# 05_SERVO_FAN.net
KiCad netlist of a schematic drawn in Altium Designer
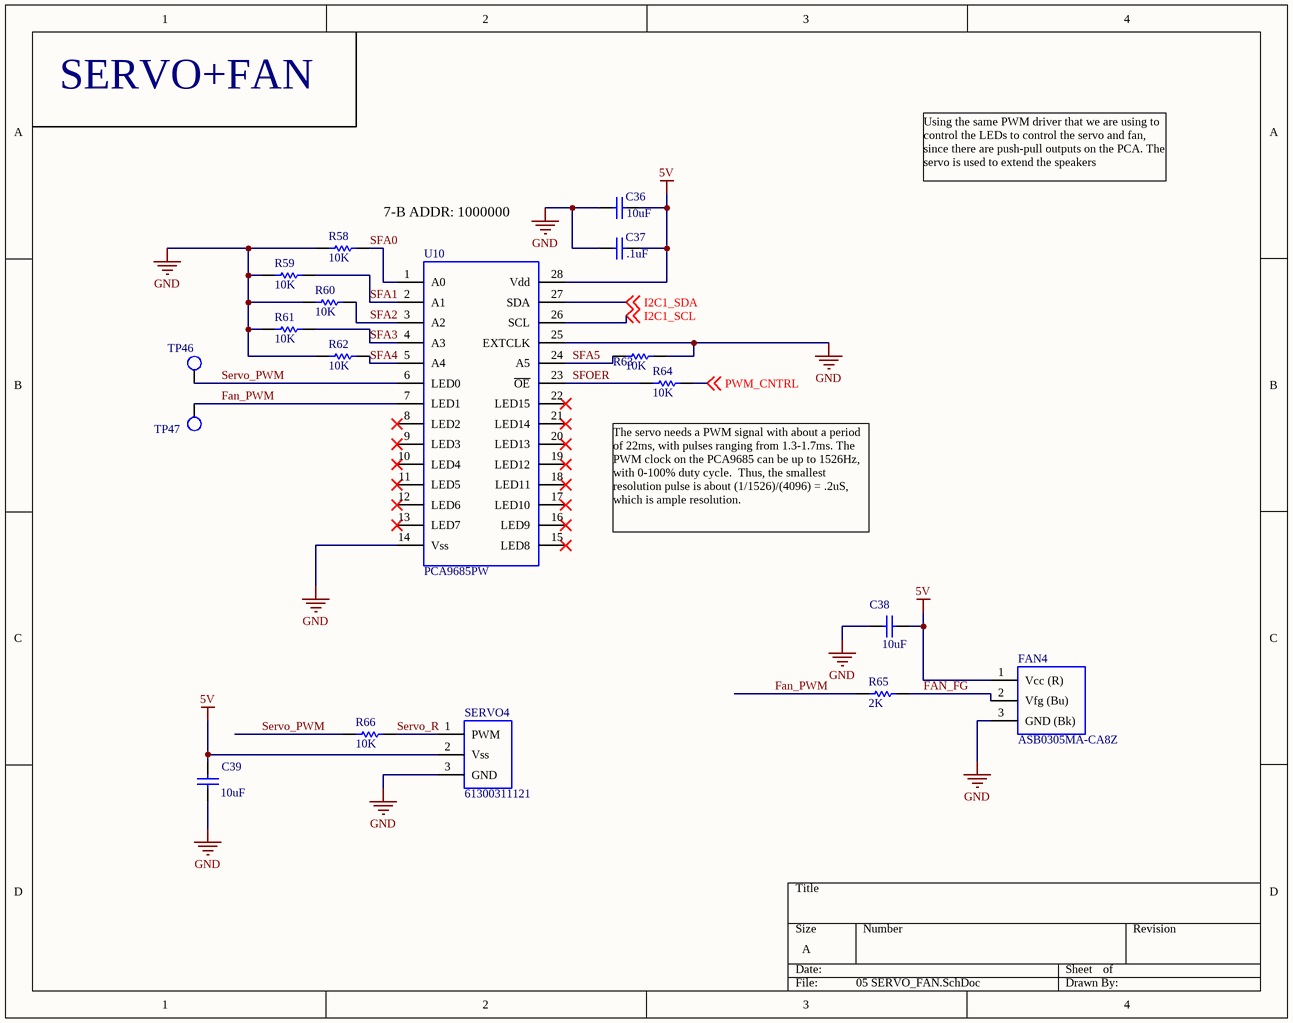
[diagram p0: 05 SERVO_FAN.SchDoc]

(export (version "E")
  (design (tool "Eeschema 10.0.6"))
  (components
    (comp (ref "C36")
      (value "10uF")
      (footprint "CAPC2012X135N")
      (description "Cap Ceramic 10uF 16V X5R 10% SMD 0805 85C T/R")
      (fields
        (field (name "MANUFACTURER") "Johanson Dielectrics")
        (field (name "MANUFACTURER PART NUMBER") "160R15X106KV4E")
      )
      (libsource (lib "schlib_truman") (part "CAP_0805_10u_16V"))
    )
    (comp (ref "C37")
      (value ".1uF")
      (footprint "CAPC2012X135N")
      (description "Cap Ceramic 0.1uF 250V X7T 10% SMD 0805 125C Plastic T/R")
      (fields
        (field (name "MANUFACTURER") "TDK")
        (field (name "MANUFACTURER PART NUMBER") "C2012X7T2E104K125AE")
      )
      (libsource (lib "schlib_truman") (part "CAP_0805_.1u_250V"))
    )
    (comp (ref "C38")
      (value "10uF")
      (footprint "CAPC2012X135N")
      (description "Cap Ceramic 10uF 16V X5R 10% SMD 0805 85C T/R")
      (fields
        (field (name "MANUFACTURER") "Johanson Dielectrics")
        (field (name "MANUFACTURER PART NUMBER") "160R15X106KV4E")
      )
      (libsource (lib "schlib_truman") (part "CAP_0805_10u_16V"))
    )
    (comp (ref "C39")
      (value "10uF")
      (footprint "CAPC2012X135N")
      (description "Cap Ceramic 10uF 16V X5R 10% SMD 0805 85C T/R")
      (fields
        (field (name "MANUFACTURER") "Johanson Dielectrics")
        (field (name "MANUFACTURER PART NUMBER") "160R15X106KV4E")
      )
      (libsource (lib "schlib_truman") (part "CAP_0805_10u_16V"))
    )
    (comp (ref "FAN4")
      (value "ASB0305MA-CA8Z")
      (footprint "FAN_HEADER")
      (description "FAN AXIAL 30X10MM 5VDC WIRE")
      (fields (field (name "MANUFACTURER") "Delta Design"))
      (libsource (lib "schlib_truman") (part "ASB0305MA-CA8Z"))
    )
    (comp (ref "R58")
      (value "RES_0805_10K")
      (footprint "RES0805")
      (description "RES, THICK FILM, 10K, 5%, 0.125W, 0805")
      (fields
        (field (name "MANUFACTURER") "Yageo")
        (field (name "MANUFACTURER PART NUMBER") "RC0805JR-0710KL")
        (field (name "RESISTANCE") "10K")
      )
      (libsource (lib "schlib_truman") (part "RES_0805_10K"))
    )
    (comp (ref "R59")
      (value "RES_0805_10K")
      (footprint "RES0805")
      (description "RES, THICK FILM, 10K, 5%, 0.125W, 0805")
      (fields
        (field (name "MANUFACTURER") "Yageo")
        (field (name "MANUFACTURER PART NUMBER") "RC0805JR-0710KL")
        (field (name "RESISTANCE") "10K")
      )
      (libsource (lib "schlib_truman") (part "RES_0805_10K"))
    )
    (comp (ref "R60")
      (value "RES_0805_10K")
      (footprint "RES0805")
      (description "RES, THICK FILM, 10K, 5%, 0.125W, 0805")
      (fields
        (field (name "MANUFACTURER") "Yageo")
        (field (name "MANUFACTURER PART NUMBER") "RC0805JR-0710KL")
        (field (name "RESISTANCE") "10K")
      )
      (libsource (lib "schlib_truman") (part "RES_0805_10K"))
    )
    (comp (ref "R61")
      (value "RES_0805_10K")
      (footprint "RES0805")
      (description "RES, THICK FILM, 10K, 5%, 0.125W, 0805")
      (fields
        (field (name "MANUFACTURER") "Yageo")
        (field (name "MANUFACTURER PART NUMBER") "RC0805JR-0710KL")
        (field (name "RESISTANCE") "10K")
      )
      (libsource (lib "schlib_truman") (part "RES_0805_10K"))
    )
    (comp (ref "R62")
      (value "RES_0805_10K")
      (footprint "RES0805")
      (description "RES, THICK FILM, 10K, 5%, 0.125W, 0805")
      (fields
        (field (name "MANUFACTURER") "Yageo")
        (field (name "MANUFACTURER PART NUMBER") "RC0805JR-0710KL")
        (field (name "RESISTANCE") "10K")
      )
      (libsource (lib "schlib_truman") (part "RES_0805_10K"))
    )
    (comp (ref "R63")
      (value "RES_0805_10K")
      (footprint "RES0805")
      (description "RES, THICK FILM, 10K, 5%, 0.125W, 0805")
      (fields
        (field (name "MANUFACTURER") "Yageo")
        (field (name "MANUFACTURER PART NUMBER") "RC0805JR-0710KL")
        (field (name "RESISTANCE") "10K")
      )
      (libsource (lib "schlib_truman") (part "RES_0805_10K"))
    )
    (comp (ref "R64")
      (value "RES_0805_10K")
      (footprint "RES0805")
      (description "RES, THICK FILM, 10K, 5%, 0.125W, 0805")
      (fields
        (field (name "MANUFACTURER") "Yageo")
        (field (name "MANUFACTURER PART NUMBER") "RC0805JR-0710KL")
        (field (name "RESISTANCE") "10K")
      )
      (libsource (lib "schlib_truman") (part "RES_0805_10K"))
    )
    (comp (ref "R65")
      (value "RES_0805_2K")
      (footprint "RES0805")
      (description "RES SMD 2K OHM 5% 1/8W 0805")
      (fields
        (field (name "MANUFACTURER") "Yageo")
        (field (name "MANUFACTURER PART NUMBER") "RC0805JR-072KL")
        (field (name "ALTIUM_UNNAMED_1") "2K")
      )
      (libsource (lib "schlib_truman") (part "RES_0805_2K"))
    )
    (comp (ref "R66")
      (value "RES_0805_10K")
      (footprint "RES0805")
      (description "RES, THICK FILM, 10K, 5%, 0.125W, 0805")
      (fields
        (field (name "MANUFACTURER") "Yageo")
        (field (name "MANUFACTURER PART NUMBER") "RC0805JR-0710KL")
        (field (name "RESISTANCE") "10K")
      )
      (libsource (lib "schlib_truman") (part "RES_0805_10K"))
    )
    (comp (ref "SERVO4")
      (value "61300311121")
      (footprint "SERVO_HEADER")
      (description "Board-To-Board Connector, Vertical, WR-PHD Series, Through Hole, Header, 3 Contacts, 2.54 mm")
      (fields (field (name "MANUFACTURER") "Wurth Electronics"))
      (libsource (lib "schlib_truman") (part "Servo_Header"))
    )
    (comp (ref "TP46")
      (value "TP")
      (footprint "TestPoint_0805")
      (description "Testpoint_0805")
      (fields
        (field (name "MANUFACTURER") "TE Connectivity")
        (field (name "MANUFACTURER PART NUMBER") "1625854-2")
      )
      (libsource (lib "schlib_truman") (part "TP"))
    )
    (comp (ref "TP47")
      (value "TP")
      (footprint "TestPoint_0805")
      (description "Testpoint_0805")
      (fields
        (field (name "MANUFACTURER") "TE Connectivity")
        (field (name "MANUFACTURER PART NUMBER") "1625854-2")
      )
      (libsource (lib "schlib_truman") (part "TP"))
    )
    (comp (ref "U10")
      (value "PCA9685PW")
      (footprint "TSSOP28")
      (description "IC LED DRIVER RGBA 28-TSSOP")
      (fields
        (field (name "MANUFACTURER") "NXP Semiconductors")
        (field (name "MANUFACTURER PART NUMBER") "PCA9685PW,118")
      )
      (libsource (lib "schlib_truman") (part "PCA9685PW"))
    )
  )
  (nets
    (net (code "1") (name "/FAN_FG") (class "Default")
      (node (ref "FAN4") (pin "2") (pinfunction "Vfg_(Bu)_2") (pintype "passive"))
      (node (ref "R65") (pin "2") (pinfunction "2_2") (pintype "passive"))
    )
    (net (code "2") (name "/Fan_PWM") (class "Default")
      (node (ref "R65") (pin "1") (pinfunction "1_1") (pintype "passive"))
      (node (ref "TP47") (pin "1") (pintype "passive"))
      (node (ref "U10") (pin "7") (pinfunction "LED1_7") (pintype "passive"))
    )
    (net (code "3") (name "/SFA0") (class "Default")
      (node (ref "R58") (pin "2") (pinfunction "2_2") (pintype "passive"))
      (node (ref "U10") (pin "1") (pinfunction "A0_1") (pintype "passive"))
    )
    (net (code "4") (name "/SFA1") (class "Default")
      (node (ref "R59") (pin "2") (pinfunction "2_2") (pintype "passive"))
      (node (ref "U10") (pin "2") (pinfunction "A1_2") (pintype "passive"))
    )
    (net (code "5") (name "/SFA2") (class "Default")
      (node (ref "R60") (pin "2") (pinfunction "2_2") (pintype "passive"))
      (node (ref "U10") (pin "3") (pinfunction "A2_3") (pintype "passive"))
    )
    (net (code "6") (name "/SFA3") (class "Default")
      (node (ref "R61") (pin "2") (pinfunction "2_2") (pintype "passive"))
      (node (ref "U10") (pin "4") (pinfunction "A3_4") (pintype "passive"))
    )
    (net (code "7") (name "/SFA4") (class "Default")
      (node (ref "R62") (pin "2") (pinfunction "2_2") (pintype "passive"))
      (node (ref "U10") (pin "5") (pinfunction "A4_5") (pintype "passive"))
    )
    (net (code "8") (name "/SFA5") (class "Default")
      (node (ref "R63") (pin "1") (pinfunction "1_1") (pintype "passive"))
      (node (ref "U10") (pin "24") (pinfunction "A5_24") (pintype "passive"))
    )
    (net (code "9") (name "/SFOER") (class "Default")
      (node (ref "R64") (pin "1") (pinfunction "1_1") (pintype "passive"))
      (node (ref "U10") (pin "23") (pinfunction "~{OE}_23") (pintype "passive"))
    )
    (net (code "10") (name "/Servo_PWM") (class "Default")
      (node (ref "R66") (pin "1") (pinfunction "1_1") (pintype "passive"))
      (node (ref "TP46") (pin "1") (pintype "passive"))
      (node (ref "U10") (pin "6") (pinfunction "LED0_6") (pintype "passive"))
    )
    (net (code "11") (name "/Servo_R") (class "Default")
      (node (ref "R66") (pin "2") (pinfunction "2_2") (pintype "passive"))
      (node (ref "SERVO4") (pin "1") (pinfunction "PWM_1") (pintype "passive"))
    )
    (net (code "12") (name "5V") (class "Default")
      (node (ref "C36") (pin "2") (pinfunction "2_2") (pintype "passive"))
      (node (ref "C37") (pin "2") (pinfunction "2_2") (pintype "passive"))
      (node (ref "C38") (pin "1") (pinfunction "1_1") (pintype "passive"))
      (node (ref "C39") (pin "2") (pinfunction "2_2") (pintype "passive"))
      (node (ref "FAN4") (pin "1") (pinfunction "Vcc_(R)_1") (pintype "passive"))
      (node (ref "SERVO4") (pin "2") (pinfunction "Vss_2") (pintype "passive"))
      (node (ref "U10") (pin "28") (pinfunction "Vdd_28") (pintype "passive"))
    )
    (net (code "13") (name "GND") (class "Default")
      (node (ref "C36") (pin "1") (pinfunction "1_1") (pintype "passive"))
      (node (ref "C37") (pin "1") (pinfunction "1_1") (pintype "passive"))
      (node (ref "C38") (pin "2") (pinfunction "2_2") (pintype "passive"))
      (node (ref "C39") (pin "1") (pinfunction "1_1") (pintype "passive"))
      (node (ref "FAN4") (pin "3") (pinfunction "GND_(Bk)_3") (pintype "passive"))
      (node (ref "R58") (pin "1") (pinfunction "1_1") (pintype "passive"))
      (node (ref "R59") (pin "1") (pinfunction "1_1") (pintype "passive"))
      (node (ref "R60") (pin "1") (pinfunction "1_1") (pintype "passive"))
      (node (ref "R61") (pin "1") (pinfunction "1_1") (pintype "passive"))
      (node (ref "R62") (pin "1") (pinfunction "1_1") (pintype "passive"))
      (node (ref "R63") (pin "2") (pinfunction "2_2") (pintype "passive"))
      (node (ref "SERVO4") (pin "3") (pinfunction "GND_3") (pintype "passive"))
      (node (ref "U10") (pin "14") (pinfunction "Vss_14") (pintype "passive"))
      (node (ref "U10") (pin "25") (pinfunction "EXTCLK_25") (pintype "passive"))
    )
    (net (code "14") (name "I2C1_SCL") (class "Default")
      (node (ref "U10") (pin "26") (pinfunction "SCL_26") (pintype "passive"))
    )
    (net (code "15") (name "I2C1_SDA") (class "Default")
      (node (ref "U10") (pin "27") (pinfunction "SDA_27") (pintype "passive"))
    )
    (net (code "16") (name "PWM_CNTRL") (class "Default")
      (node (ref "R64") (pin "2") (pinfunction "2_2") (pintype "passive"))
    )
    (net (code "17") (name "unconnected-(U10-LED2-Pad8)") (class "Default")
      (node (ref "U10") (pin "8") (pinfunction "LED2_8") (pintype "passive+no_connect"))
    )
    (net (code "18") (name "unconnected-(U10-LED3-Pad9)") (class "Default")
      (node (ref "U10") (pin "9") (pinfunction "LED3_9") (pintype "passive+no_connect"))
    )
    (net (code "19") (name "unconnected-(U10-LED4-Pad10)") (class "Default")
      (node (ref "U10") (pin "10") (pinfunction "LED4_10") (pintype "passive+no_connect"))
    )
    (net (code "20") (name "unconnected-(U10-LED5-Pad11)") (class "Default")
      (node (ref "U10") (pin "11") (pinfunction "LED5_11") (pintype "passive+no_connect"))
    )
    (net (code "21") (name "unconnected-(U10-LED6-Pad12)") (class "Default")
      (node (ref "U10") (pin "12") (pinfunction "LED6_12") (pintype "passive+no_connect"))
    )
    (net (code "22") (name "unconnected-(U10-LED7-Pad13)") (class "Default")
      (node (ref "U10") (pin "13") (pinfunction "LED7_13") (pintype "passive+no_connect"))
    )
    (net (code "23") (name "unconnected-(U10-LED8-Pad15)") (class "Default")
      (node (ref "U10") (pin "15") (pinfunction "LED8_15") (pintype "passive+no_connect"))
    )
    (net (code "24") (name "unconnected-(U10-LED9-Pad16)") (class "Default")
      (node (ref "U10") (pin "16") (pinfunction "LED9_16") (pintype "passive+no_connect"))
    )
    (net (code "25") (name "unconnected-(U10-LED10-Pad17)") (class "Default")
      (node (ref "U10") (pin "17") (pinfunction "LED10_17") (pintype "passive+no_connect"))
    )
    (net (code "26") (name "unconnected-(U10-LED11-Pad18)") (class "Default")
      (node (ref "U10") (pin "18") (pinfunction "LED11_18") (pintype "passive+no_connect"))
    )
    (net (code "27") (name "unconnected-(U10-LED12-Pad19)") (class "Default")
      (node (ref "U10") (pin "19") (pinfunction "LED12_19") (pintype "passive+no_connect"))
    )
    (net (code "28") (name "unconnected-(U10-LED13-Pad20)") (class "Default")
      (node (ref "U10") (pin "20") (pinfunction "LED13_20") (pintype "passive+no_connect"))
    )
    (net (code "29") (name "unconnected-(U10-LED14-Pad21)") (class "Default")
      (node (ref "U10") (pin "21") (pinfunction "LED14_21") (pintype "passive+no_connect"))
    )
    (net (code "30") (name "unconnected-(U10-LED15-Pad22)") (class "Default")
      (node (ref "U10") (pin "22") (pinfunction "LED15_22") (pintype "passive+no_connect"))
    )
  )
)
